# eGAN-FET-module_Amplifier.net
KiCad netlist of a schematic drawn in Altium Designer
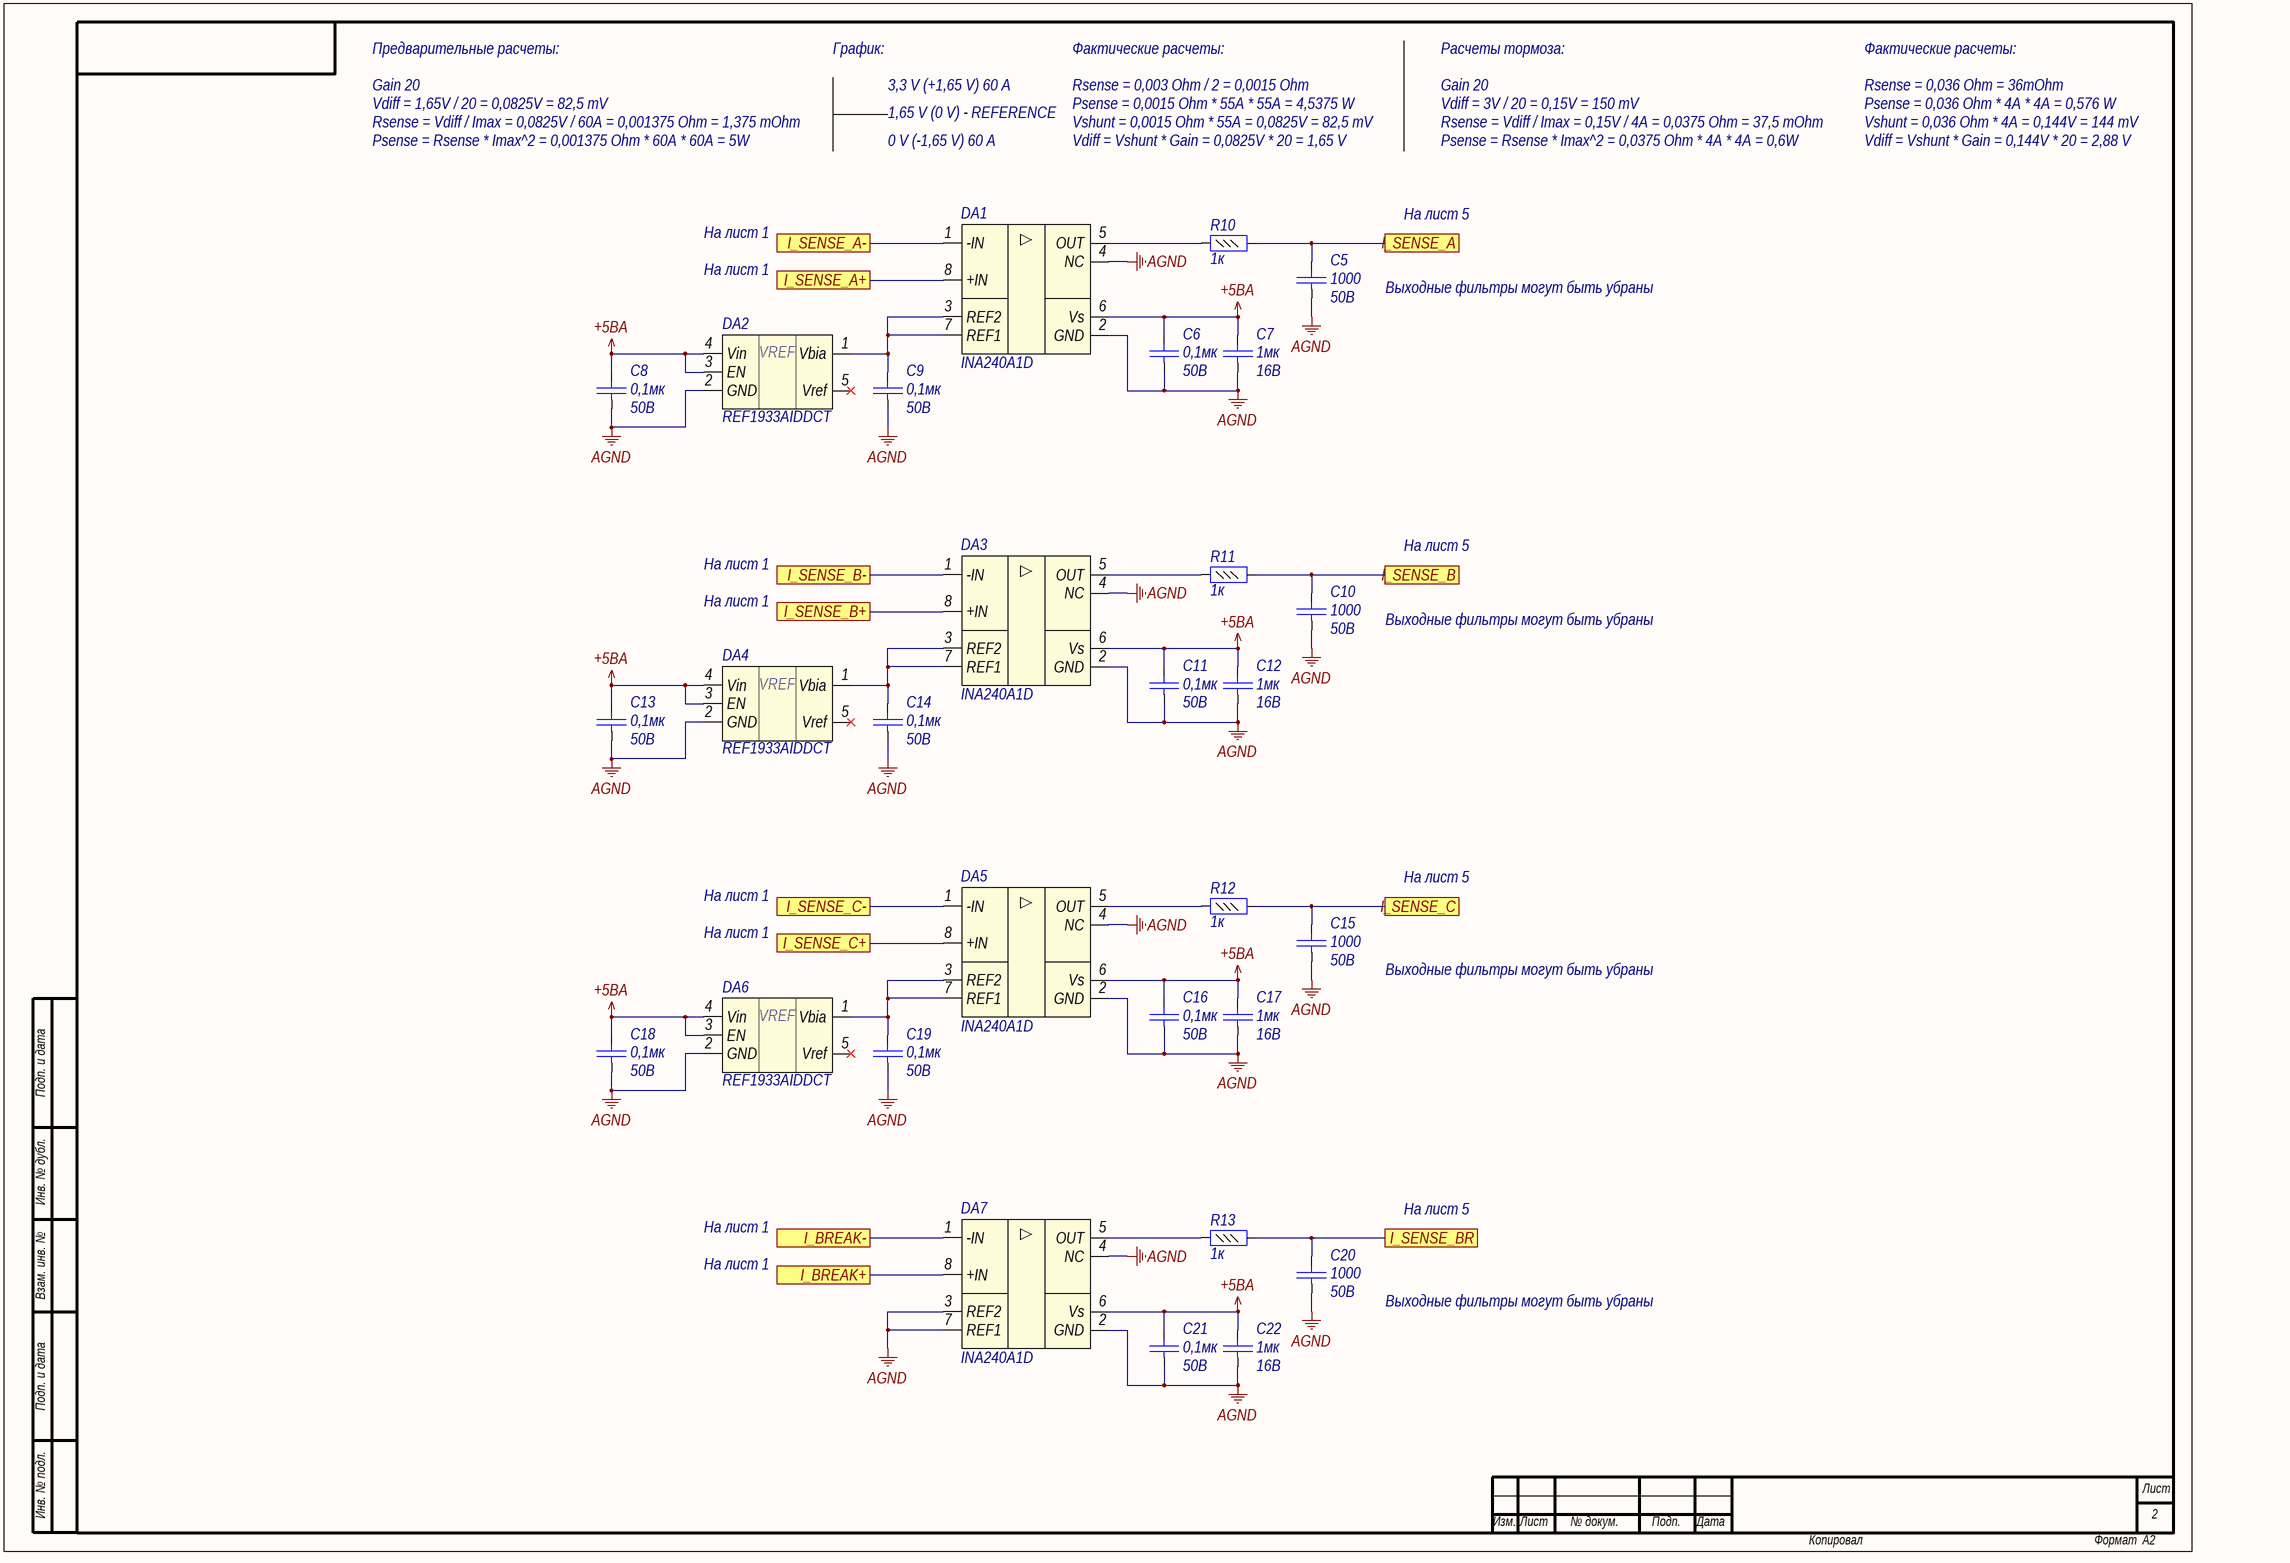
[diagram p0: eGAN-FET-module_Amplifier.SchDoc]

(export (version "E")
  (design (tool "Eeschema 10.0.6"))
  (components
    (comp (ref "C5")
      (value "1000")
      (footprint "C0402")
      (description "Конденсатор")
      (fields
        (field (name "VOLTAGE") "50B")
        (field (name "PART NUMBER") "GRM1555C1H102J")
        (field (name "Comment") "Capacitor")
      )
      (libsource (lib "MOP44") (part "Capacitor"))
    )
    (comp (ref "C6")
      (value "0,1мк")
      (footprint "C0402")
      (description "Конденсатор")
      (fields
        (field (name "VOLTAGE") "50В")
        (field (name "PART NUMBER") "GRM155R71H104KE14D")
        (field (name "Comment") "Capacitor")
      )
      (libsource (lib "MOP44") (part "Capacitor"))
    )
    (comp (ref "C7")
      (value "1мк")
      (footprint "C0402")
      (description "Конденсатор")
      (fields (field (name "VOLTAGE") "16B") (field (name "PART NUMBER") "EMK105BJ105KV-F"))
      (libsource (lib "") (part "Capacitor_1"))
    )
    (comp (ref "C8")
      (value "0,1мк")
      (footprint "C0402")
      (description "Конденсатор")
      (fields
        (field (name "VOLTAGE") "50В")
        (field (name "PART NUMBER") "GRM155R71H104KE14D")
        (field (name "Comment") "Capacitor")
      )
      (libsource (lib "MOP44") (part "Capacitor"))
    )
    (comp (ref "C9")
      (value "0,1мк")
      (footprint "C0402")
      (description "Конденсатор")
      (fields
        (field (name "VOLTAGE") "50В")
        (field (name "PART NUMBER") "GRM155R71H104KE14D")
        (field (name "Comment") "Capacitor")
      )
      (libsource (lib "MOP44") (part "Capacitor"))
    )
    (comp (ref "C10")
      (value "1000")
      (footprint "C0402")
      (description "Конденсатор")
      (fields
        (field (name "VOLTAGE") "50B")
        (field (name "PART NUMBER") "GRM1555C1H102J")
        (field (name "Comment") "Capacitor")
      )
      (libsource (lib "MOP44") (part "Capacitor"))
    )
    (comp (ref "C11")
      (value "0,1мк")
      (footprint "C0402")
      (description "Конденсатор")
      (fields
        (field (name "VOLTAGE") "50В")
        (field (name "PART NUMBER") "GRM155R71H104KE14D")
        (field (name "Comment") "Capacitor")
      )
      (libsource (lib "MOP44") (part "Capacitor"))
    )
    (comp (ref "C12")
      (value "1мк")
      (footprint "C0402")
      (description "Конденсатор")
      (fields (field (name "VOLTAGE") "16B") (field (name "PART NUMBER") "EMK105BJ105KV-F"))
      (libsource (lib "") (part "Capacitor_1"))
    )
    (comp (ref "C13")
      (value "0,1мк")
      (footprint "C0402")
      (description "Конденсатор")
      (fields
        (field (name "VOLTAGE") "50В")
        (field (name "PART NUMBER") "GRM155R71H104KE14D")
        (field (name "Comment") "Capacitor")
      )
      (libsource (lib "MOP44") (part "Capacitor"))
    )
    (comp (ref "C14")
      (value "0,1мк")
      (footprint "C0402")
      (description "Конденсатор")
      (fields
        (field (name "VOLTAGE") "50В")
        (field (name "PART NUMBER") "GRM155R71H104KE14D")
        (field (name "Comment") "Capacitor")
      )
      (libsource (lib "MOP44") (part "Capacitor"))
    )
    (comp (ref "C15")
      (value "1000")
      (footprint "C0402")
      (description "Конденсатор")
      (fields
        (field (name "VOLTAGE") "50B")
        (field (name "PART NUMBER") "GRM1555C1H102J")
        (field (name "Comment") "Capacitor")
      )
      (libsource (lib "MOP44") (part "Capacitor"))
    )
    (comp (ref "C16")
      (value "0,1мк")
      (footprint "C0402")
      (description "Конденсатор")
      (fields
        (field (name "VOLTAGE") "50В")
        (field (name "PART NUMBER") "GRM155R71H104KE14D")
        (field (name "Comment") "Capacitor")
      )
      (libsource (lib "MOP44") (part "Capacitor"))
    )
    (comp (ref "C17")
      (value "1мк")
      (footprint "C0402")
      (description "Конденсатор")
      (fields (field (name "VOLTAGE") "16B") (field (name "PART NUMBER") "EMK105BJ105KV-F"))
      (libsource (lib "") (part "Capacitor_1"))
    )
    (comp (ref "C18")
      (value "0,1мк")
      (footprint "C0402")
      (description "Конденсатор")
      (fields
        (field (name "VOLTAGE") "50В")
        (field (name "PART NUMBER") "GRM155R71H104KE14D")
        (field (name "Comment") "Capacitor")
      )
      (libsource (lib "MOP44") (part "Capacitor"))
    )
    (comp (ref "C19")
      (value "0,1мк")
      (footprint "C0402")
      (description "Конденсатор")
      (fields
        (field (name "VOLTAGE") "50В")
        (field (name "PART NUMBER") "GRM155R71H104KE14D")
        (field (name "Comment") "Capacitor")
      )
      (libsource (lib "MOP44") (part "Capacitor"))
    )
    (comp (ref "C20")
      (value "1000")
      (footprint "C0402")
      (description "Конденсатор")
      (fields
        (field (name "VOLTAGE") "50B")
        (field (name "PART NUMBER") "GRM1555C1H102J")
        (field (name "Comment") "Capacitor")
      )
      (libsource (lib "MOP44") (part "Capacitor"))
    )
    (comp (ref "C21")
      (value "0,1мк")
      (footprint "C0402")
      (description "Конденсатор")
      (fields
        (field (name "VOLTAGE") "50В")
        (field (name "PART NUMBER") "GRM155R71H104KE14D")
        (field (name "Comment") "Capacitor")
      )
      (libsource (lib "MOP44") (part "Capacitor"))
    )
    (comp (ref "C22")
      (value "1мк")
      (footprint "C0402")
      (description "Конденсатор")
      (fields (field (name "VOLTAGE") "16B") (field (name "PART NUMBER") "EMK105BJ105KV-F"))
      (libsource (lib "") (part "Capacitor_1"))
    )
    (comp (ref "DA1")
      (value "INA240A1D")
      (footprint "SO8")
      (description "–4-V to 80-V, Bidirectional, Ultra-Precise Current Sense Amplifier With\r\nEnhanced PWM Rejection")
      (libsource (lib "MOP44") (part "INA240"))
    )
    (comp (ref "DA2")
      (value "REF1933AIDDCT")
      (footprint "SOT23-5")
      (description ", Dual-Output, VREF and VREF / 2 Voltage References")
      (fields (field (name "MANUFACTURER") "Texas Instruments"))
      (libsource (lib "MOP44") (part "REF19xx"))
    )
    (comp (ref "DA3")
      (value "INA240A1D")
      (footprint "SO8")
      (description "–4-V to 80-V, Bidirectional, Ultra-Precise Current Sense Amplifier With\r\nEnhanced PWM Rejection")
      (libsource (lib "MOP44") (part "INA240"))
    )
    (comp (ref "DA4")
      (value "REF1933AIDDCT")
      (footprint "SOT23-5")
      (description ", Dual-Output, VREF and VREF / 2 Voltage References")
      (fields (field (name "MANUFACTURER") "Texas Instruments"))
      (libsource (lib "MOP44") (part "REF19xx"))
    )
    (comp (ref "DA5")
      (value "INA240A1D")
      (footprint "SO8")
      (description "–4-V to 80-V, Bidirectional, Ultra-Precise Current Sense Amplifier With\r\nEnhanced PWM Rejection")
      (libsource (lib "MOP44") (part "INA240"))
    )
    (comp (ref "DA6")
      (value "REF1933AIDDCT")
      (footprint "SOT23-5")
      (description ", Dual-Output, VREF and VREF / 2 Voltage References")
      (fields (field (name "MANUFACTURER") "Texas Instruments"))
      (libsource (lib "MOP44") (part "REF19xx"))
    )
    (comp (ref "DA7")
      (value "INA240A1D")
      (footprint "SO8")
      (description "–4-V to 80-V, Bidirectional, Ultra-Precise Current Sense Amplifier With\r\nEnhanced PWM Rejection")
      (libsource (lib "MOP44") (part "INA240"))
    )
    (comp (ref "R10")
      (value "1к")
      (footprint "R0402")
      (description "Резистор")
      (fields (field (name "PART NUMBER") "RC0402FR-071KL") (field (name "POWER") "0,062Вт"))
      (libsource (lib "MOP44") (part "Resistor_0,062Вт"))
    )
    (comp (ref "R11")
      (value "1к")
      (footprint "R0402")
      (description "Резистор")
      (fields (field (name "PART NUMBER") "RC0402FR-071KL") (field (name "POWER") "0,062Вт"))
      (libsource (lib "MOP44") (part "Resistor_0,062Вт"))
    )
    (comp (ref "R12")
      (value "1к")
      (footprint "R0402")
      (description "Резистор")
      (fields (field (name "PART NUMBER") "RC0402FR-071KL") (field (name "POWER") "0,062Вт"))
      (libsource (lib "MOP44") (part "Resistor_0,062Вт"))
    )
    (comp (ref "R13")
      (value "1к")
      (footprint "R0402")
      (description "Резистор")
      (fields (field (name "PART NUMBER") "RC0402FR-071KL") (field (name "POWER") "0,062Вт"))
      (libsource (lib "MOP44") (part "Resistor_0,062Вт"))
    )
  )
  (nets
    (net (code "1") (name "+5BA") (class "Default")
      (node (ref "C11") (pin "2") (pinfunction "2_2") (pintype "passive"))
      (node (ref "C12") (pin "2") (pinfunction "2_2") (pintype "passive"))
      (node (ref "C13") (pin "2") (pinfunction "2_2") (pintype "passive"))
      (node (ref "C16") (pin "2") (pinfunction "2_2") (pintype "passive"))
      (node (ref "C17") (pin "2") (pinfunction "2_2") (pintype "passive"))
      (node (ref "C18") (pin "2") (pinfunction "2_2") (pintype "passive"))
      (node (ref "C21") (pin "2") (pinfunction "2_2") (pintype "passive"))
      (node (ref "C22") (pin "2") (pinfunction "2_2") (pintype "passive"))
      (node (ref "C6") (pin "2") (pinfunction "2_2") (pintype "passive"))
      (node (ref "C7") (pin "2") (pinfunction "2_2") (pintype "passive"))
      (node (ref "C8") (pin "2") (pinfunction "2_2") (pintype "passive"))
      (node (ref "DA1") (pin "6") (pinfunction "Vs_6") (pintype "passive"))
      (node (ref "DA2") (pin "3") (pinfunction "EN_3") (pintype "passive"))
      (node (ref "DA2") (pin "4") (pinfunction "Vin_4") (pintype "passive"))
      (node (ref "DA3") (pin "6") (pinfunction "Vs_6") (pintype "passive"))
      (node (ref "DA4") (pin "3") (pinfunction "EN_3") (pintype "passive"))
      (node (ref "DA4") (pin "4") (pinfunction "Vin_4") (pintype "passive"))
      (node (ref "DA5") (pin "6") (pinfunction "Vs_6") (pintype "passive"))
      (node (ref "DA6") (pin "3") (pinfunction "EN_3") (pintype "passive"))
      (node (ref "DA6") (pin "4") (pinfunction "Vin_4") (pintype "passive"))
      (node (ref "DA7") (pin "6") (pinfunction "Vs_6") (pintype "passive"))
    )
    (net (code "2") (name "/I_BREAK+") (class "Default")
      (node (ref "DA7") (pin "8") (pinfunction "+IN_8") (pintype "passive"))
    )
    (net (code "3") (name "/I_BREAK-") (class "Default")
      (node (ref "DA7") (pin "1") (pinfunction "-IN_1") (pintype "passive"))
    )
    (net (code "4") (name "/I_SENSE_A") (class "Default")
      (node (ref "C5") (pin "2") (pinfunction "2_2") (pintype "passive"))
      (node (ref "R10") (pin "2") (pinfunction "2_2") (pintype "passive"))
    )
    (net (code "5") (name "/I_SENSE_A+") (class "Default")
      (node (ref "DA1") (pin "8") (pinfunction "+IN_8") (pintype "passive"))
    )
    (net (code "6") (name "/I_SENSE_A-") (class "Default")
      (node (ref "DA1") (pin "1") (pinfunction "-IN_1") (pintype "passive"))
    )
    (net (code "7") (name "/I_SENSE_B") (class "Default")
      (node (ref "C10") (pin "2") (pinfunction "2_2") (pintype "passive"))
      (node (ref "R11") (pin "2") (pinfunction "2_2") (pintype "passive"))
    )
    (net (code "8") (name "/I_SENSE_B+") (class "Default")
      (node (ref "DA3") (pin "8") (pinfunction "+IN_8") (pintype "passive"))
    )
    (net (code "9") (name "/I_SENSE_B-") (class "Default")
      (node (ref "DA3") (pin "1") (pinfunction "-IN_1") (pintype "passive"))
    )
    (net (code "10") (name "/I_SENSE_BR") (class "Default")
      (node (ref "C20") (pin "2") (pinfunction "2_2") (pintype "passive"))
      (node (ref "R13") (pin "2") (pinfunction "2_2") (pintype "passive"))
    )
    (net (code "11") (name "/I_SENSE_C") (class "Default")
      (node (ref "C15") (pin "2") (pinfunction "2_2") (pintype "passive"))
      (node (ref "R12") (pin "2") (pinfunction "2_2") (pintype "passive"))
    )
    (net (code "12") (name "/I_SENSE_C+") (class "Default")
      (node (ref "DA5") (pin "8") (pinfunction "+IN_8") (pintype "passive"))
    )
    (net (code "13") (name "/I_SENSE_C-") (class "Default")
      (node (ref "DA5") (pin "1") (pinfunction "-IN_1") (pintype "passive"))
    )
    (net (code "14") (name "AGND") (class "Default")
      (node (ref "C10") (pin "1") (pinfunction "1_1") (pintype "passive"))
      (node (ref "C11") (pin "1") (pinfunction "1_1") (pintype "passive"))
      (node (ref "C12") (pin "1") (pinfunction "1_1") (pintype "passive"))
      (node (ref "C13") (pin "1") (pinfunction "1_1") (pintype "passive"))
      (node (ref "C14") (pin "1") (pinfunction "1_1") (pintype "passive"))
      (node (ref "C15") (pin "1") (pinfunction "1_1") (pintype "passive"))
      (node (ref "C16") (pin "1") (pinfunction "1_1") (pintype "passive"))
      (node (ref "C17") (pin "1") (pinfunction "1_1") (pintype "passive"))
      (node (ref "C18") (pin "1") (pinfunction "1_1") (pintype "passive"))
      (node (ref "C19") (pin "1") (pinfunction "1_1") (pintype "passive"))
      (node (ref "C20") (pin "1") (pinfunction "1_1") (pintype "passive"))
      (node (ref "C21") (pin "1") (pinfunction "1_1") (pintype "passive"))
      (node (ref "C22") (pin "1") (pinfunction "1_1") (pintype "passive"))
      (node (ref "C5") (pin "1") (pinfunction "1_1") (pintype "passive"))
      (node (ref "C6") (pin "1") (pinfunction "1_1") (pintype "passive"))
      (node (ref "C7") (pin "1") (pinfunction "1_1") (pintype "passive"))
      (node (ref "C8") (pin "1") (pinfunction "1_1") (pintype "passive"))
      (node (ref "C9") (pin "1") (pinfunction "1_1") (pintype "passive"))
      (node (ref "DA1") (pin "2") (pinfunction "GND_2") (pintype "passive"))
      (node (ref "DA1") (pin "4") (pinfunction "NC_4") (pintype "passive"))
      (node (ref "DA2") (pin "2") (pinfunction "GND_2") (pintype "passive"))
      (node (ref "DA3") (pin "2") (pinfunction "GND_2") (pintype "passive"))
      (node (ref "DA3") (pin "4") (pinfunction "NC_4") (pintype "passive"))
      (node (ref "DA4") (pin "2") (pinfunction "GND_2") (pintype "passive"))
      (node (ref "DA5") (pin "2") (pinfunction "GND_2") (pintype "passive"))
      (node (ref "DA5") (pin "4") (pinfunction "NC_4") (pintype "passive"))
      (node (ref "DA6") (pin "2") (pinfunction "GND_2") (pintype "passive"))
      (node (ref "DA7") (pin "2") (pinfunction "GND_2") (pintype "passive"))
      (node (ref "DA7") (pin "3") (pinfunction "REF2_3") (pintype "passive"))
      (node (ref "DA7") (pin "4") (pinfunction "NC_4") (pintype "passive"))
      (node (ref "DA7") (pin "7") (pinfunction "REF1_7") (pintype "passive"))
    )
    (net (code "15") (name "Net-(DA1-OUT)") (class "Default")
      (node (ref "DA1") (pin "5") (pinfunction "OUT_5") (pintype "passive"))
      (node (ref "R10") (pin "1") (pinfunction "1_1") (pintype "passive"))
    )
    (net (code "16") (name "Net-(DA1-REF1)") (class "Default")
      (node (ref "C9") (pin "2") (pinfunction "2_2") (pintype "passive"))
      (node (ref "DA1") (pin "3") (pinfunction "REF2_3") (pintype "passive"))
      (node (ref "DA1") (pin "7") (pinfunction "REF1_7") (pintype "passive"))
      (node (ref "DA2") (pin "1") (pinfunction "Vbia_1") (pintype "passive"))
    )
    (net (code "17") (name "Net-(DA3-OUT)") (class "Default")
      (node (ref "DA3") (pin "5") (pinfunction "OUT_5") (pintype "passive"))
      (node (ref "R11") (pin "1") (pinfunction "1_1") (pintype "passive"))
    )
    (net (code "18") (name "Net-(DA3-REF1)") (class "Default")
      (node (ref "C14") (pin "2") (pinfunction "2_2") (pintype "passive"))
      (node (ref "DA3") (pin "3") (pinfunction "REF2_3") (pintype "passive"))
      (node (ref "DA3") (pin "7") (pinfunction "REF1_7") (pintype "passive"))
      (node (ref "DA4") (pin "1") (pinfunction "Vbia_1") (pintype "passive"))
    )
    (net (code "19") (name "Net-(DA5-OUT)") (class "Default")
      (node (ref "DA5") (pin "5") (pinfunction "OUT_5") (pintype "passive"))
      (node (ref "R12") (pin "1") (pinfunction "1_1") (pintype "passive"))
    )
    (net (code "20") (name "Net-(DA5-REF1)") (class "Default")
      (node (ref "C19") (pin "2") (pinfunction "2_2") (pintype "passive"))
      (node (ref "DA5") (pin "3") (pinfunction "REF2_3") (pintype "passive"))
      (node (ref "DA5") (pin "7") (pinfunction "REF1_7") (pintype "passive"))
      (node (ref "DA6") (pin "1") (pinfunction "Vbia_1") (pintype "passive"))
    )
    (net (code "21") (name "Net-(DA7-OUT)") (class "Default")
      (node (ref "DA7") (pin "5") (pinfunction "OUT_5") (pintype "passive"))
      (node (ref "R13") (pin "1") (pinfunction "1_1") (pintype "passive"))
    )
    (net (code "22") (name "unconnected-(DA2-Vref-Pad5)") (class "Default")
      (node (ref "DA2") (pin "5") (pinfunction "Vref_5") (pintype "passive+no_connect"))
    )
    (net (code "23") (name "unconnected-(DA4-Vref-Pad5)") (class "Default")
      (node (ref "DA4") (pin "5") (pinfunction "Vref_5") (pintype "passive+no_connect"))
    )
    (net (code "24") (name "unconnected-(DA6-Vref-Pad5)") (class "Default")
      (node (ref "DA6") (pin "5") (pinfunction "Vref_5") (pintype "passive+no_connect"))
    )
  )
)
